# VauDUOv1_2.net
KiCad netlist of a schematic drawn in EAGLE
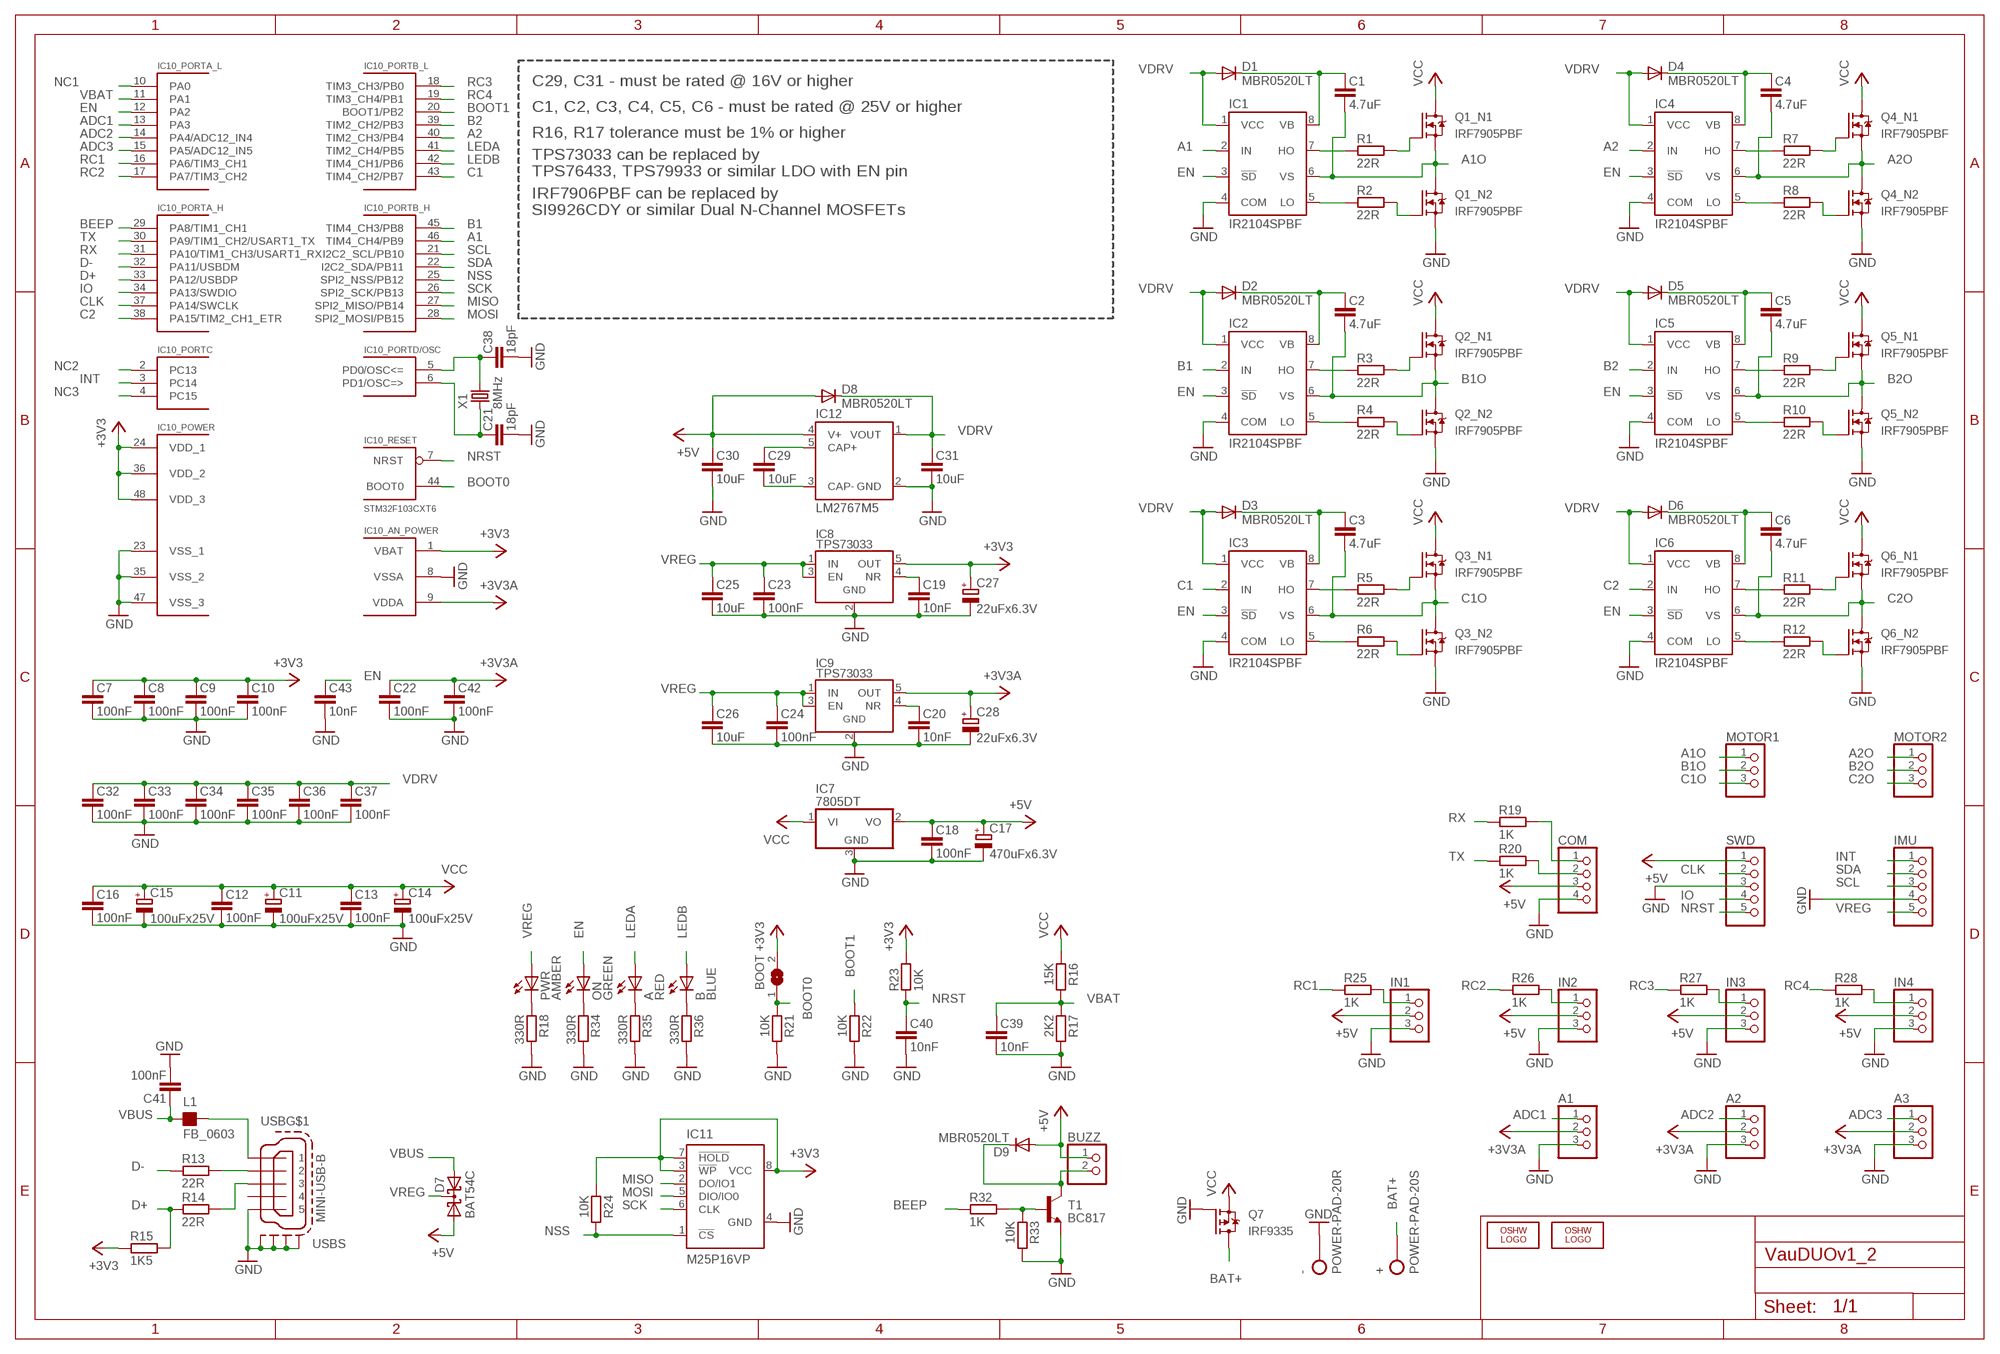
[diagram p0: schematic, sheet 1]

(export (version "E")
  (design (tool "Eeschema 10.0.6"))
  (components
    (comp (ref "+")
      (value "POWER-PAD-20S")
      (footprint "eagle-import:PAD20S")
      (libsource (lib "eagle-import") (part "POWER-PAD-20S"))
    )
    (comp (ref "-")
      (value "POWER-PAD-20R")
      (footprint "eagle-import:PAD20R")
      (libsource (lib "eagle-import") (part "POWER-PAD-20R"))
    )
    (comp (ref "A")
      (value "RED")
      (footprint "eagle-import:CHIPLED_0805")
      (libsource (lib "eagle-import") (part "LEDCHIPLED_0805"))
    )
    (comp (ref "A1")
      (value "PINHD-1X3")
      (footprint "eagle-import:1X03")
      (libsource (lib "eagle-import") (part "PINHD-1X3"))
    )
    (comp (ref "A2")
      (value "PINHD-1X3")
      (footprint "eagle-import:1X03")
      (libsource (lib "eagle-import") (part "PINHD-1X3"))
    )
    (comp (ref "A3")
      (value "PINHD-1X3")
      (footprint "eagle-import:1X03")
      (libsource (lib "eagle-import") (part "PINHD-1X3"))
    )
    (comp (ref "B")
      (value "BLUE")
      (footprint "eagle-import:CHIPLED_0805")
      (libsource (lib "eagle-import") (part "LEDCHIPLED_0805"))
    )
    (comp (ref "BOOT")
      (value "SJ")
      (footprint "eagle-import:SJ")
      (libsource (lib "eagle-import") (part "SJ"))
    )
    (comp (ref "BUZZ")
      (value "PINHD-1X2")
      (footprint "eagle-import:1X02")
      (libsource (lib "eagle-import") (part "PINHD-1X2"))
    )
    (comp (ref "C1")
      (value "4.7uF")
      (footprint "eagle-import:C0805")
      (libsource (lib "eagle-import") (part "C_EU_C0805"))
    )
    (comp (ref "C2")
      (value "4.7uF")
      (footprint "eagle-import:C0805")
      (libsource (lib "eagle-import") (part "C_EU_C0805"))
    )
    (comp (ref "C3")
      (value "4.7uF")
      (footprint "eagle-import:C0805")
      (libsource (lib "eagle-import") (part "C_EU_C0805"))
    )
    (comp (ref "C4")
      (value "4.7uF")
      (footprint "eagle-import:C0805")
      (libsource (lib "eagle-import") (part "C_EU_C0805"))
    )
    (comp (ref "C5")
      (value "4.7uF")
      (footprint "eagle-import:C0805")
      (libsource (lib "eagle-import") (part "C_EU_C0805"))
    )
    (comp (ref "C6")
      (value "4.7uF")
      (footprint "eagle-import:C0805")
      (libsource (lib "eagle-import") (part "C_EU_C0805"))
    )
    (comp (ref "C7")
      (value "100nF")
      (footprint "eagle-import:C0603G")
      (libsource (lib "eagle-import") (part "C_EU_C0603G"))
    )
    (comp (ref "C8")
      (value "100nF")
      (footprint "eagle-import:C0603G")
      (libsource (lib "eagle-import") (part "C_EU_C0603G"))
    )
    (comp (ref "C9")
      (value "100nF")
      (footprint "eagle-import:C0603G")
      (libsource (lib "eagle-import") (part "C_EU_C0603G"))
    )
    (comp (ref "C10")
      (value "100nF")
      (footprint "eagle-import:C0603G")
      (libsource (lib "eagle-import") (part "C_EU_C0603G"))
    )
    (comp (ref "C11")
      (value "100uFx25V")
      (footprint "eagle-import:E2,5-7")
      (libsource (lib "eagle-import") (part "CPOL-EUE2.5-7"))
    )
    (comp (ref "C12")
      (value "100nF")
      (footprint "eagle-import:C0603G")
      (libsource (lib "eagle-import") (part "C_EU_C0603G"))
    )
    (comp (ref "C13")
      (value "100nF")
      (footprint "eagle-import:C0603G")
      (libsource (lib "eagle-import") (part "C_EU_C0603G"))
    )
    (comp (ref "C14")
      (value "100uFx25V")
      (footprint "eagle-import:E2,5-7")
      (libsource (lib "eagle-import") (part "CPOL-EUE2.5-7"))
    )
    (comp (ref "C15")
      (value "100uFx25V")
      (footprint "eagle-import:SMC_D")
      (libsource (lib "eagle-import") (part "CPOL-EUSMCD"))
    )
    (comp (ref "C16")
      (value "100nF")
      (footprint "eagle-import:C0603G")
      (libsource (lib "eagle-import") (part "C_EU_C0603G"))
    )
    (comp (ref "C17")
      (value "470uFx6.3V")
      (footprint "eagle-import:SMC_D")
      (libsource (lib "eagle-import") (part "CPOL-EUSMCD"))
    )
    (comp (ref "C18")
      (value "100nF")
      (footprint "eagle-import:C0603G")
      (libsource (lib "eagle-import") (part "C_EU_C0603G"))
    )
    (comp (ref "C19")
      (value "10nF")
      (footprint "eagle-import:C0603G")
      (libsource (lib "eagle-import") (part "C_EU_C0603G"))
    )
    (comp (ref "C20")
      (value "10nF")
      (footprint "eagle-import:C0603G")
      (libsource (lib "eagle-import") (part "C_EU_C0603G"))
    )
    (comp (ref "C21")
      (value "18pF")
      (footprint "eagle-import:C0603G")
      (libsource (lib "eagle-import") (part "C_EU_C0603G"))
    )
    (comp (ref "C22")
      (value "100nF")
      (footprint "eagle-import:C0603G")
      (libsource (lib "eagle-import") (part "C_EU_C0603G"))
    )
    (comp (ref "C23")
      (value "100nF")
      (footprint "eagle-import:C0603G")
      (libsource (lib "eagle-import") (part "C_EU_C0603G"))
    )
    (comp (ref "C24")
      (value "100nF")
      (footprint "eagle-import:C0603G")
      (libsource (lib "eagle-import") (part "C_EU_C0603G"))
    )
    (comp (ref "C25")
      (value "10uF")
      (footprint "eagle-import:C0805G")
      (libsource (lib "eagle-import") (part "C_EU_C0805G"))
    )
    (comp (ref "C26")
      (value "10uF")
      (footprint "eagle-import:C0805G")
      (libsource (lib "eagle-import") (part "C_EU_C0805G"))
    )
    (comp (ref "C27")
      (value "22uFx6.3V")
      (footprint "eagle-import:SMC_A")
      (libsource (lib "eagle-import") (part "CPOL-EUSMCA"))
    )
    (comp (ref "C28")
      (value "22uFx6.3V")
      (footprint "eagle-import:SMC_A")
      (libsource (lib "eagle-import") (part "CPOL-EUSMCA"))
    )
    (comp (ref "C29")
      (value "10uF")
      (footprint "eagle-import:C0805")
      (libsource (lib "eagle-import") (part "C_EU_C0805"))
    )
    (comp (ref "C30")
      (value "10uF")
      (footprint "eagle-import:C0805G")
      (libsource (lib "eagle-import") (part "C_EU_C0805G"))
    )
    (comp (ref "C31")
      (value "10uF")
      (footprint "eagle-import:C0805G")
      (libsource (lib "eagle-import") (part "C_EU_C0805G"))
    )
    (comp (ref "C32")
      (value "100nF")
      (footprint "eagle-import:C0603G")
      (libsource (lib "eagle-import") (part "C_EU_C0603G"))
    )
    (comp (ref "C33")
      (value "100nF")
      (footprint "eagle-import:C0603G")
      (libsource (lib "eagle-import") (part "C_EU_C0603G"))
    )
    (comp (ref "C34")
      (value "100nF")
      (footprint "eagle-import:C0603G")
      (libsource (lib "eagle-import") (part "C_EU_C0603G"))
    )
    (comp (ref "C35")
      (value "100nF")
      (footprint "eagle-import:C0603G")
      (libsource (lib "eagle-import") (part "C_EU_C0603G"))
    )
    (comp (ref "C36")
      (value "100nF")
      (footprint "eagle-import:C0603G")
      (libsource (lib "eagle-import") (part "C_EU_C0603G"))
    )
    (comp (ref "C37")
      (value "100nF")
      (footprint "eagle-import:C0603G")
      (libsource (lib "eagle-import") (part "C_EU_C0603G"))
    )
    (comp (ref "C38")
      (value "18pF")
      (footprint "eagle-import:C0603G")
      (libsource (lib "eagle-import") (part "C_EU_C0603G"))
    )
    (comp (ref "C39")
      (value "10nF")
      (footprint "eagle-import:C0603G")
      (libsource (lib "eagle-import") (part "C_EU_C0603G"))
    )
    (comp (ref "C40")
      (value "10nF")
      (footprint "eagle-import:C0603G")
      (libsource (lib "eagle-import") (part "C_EU_C0603G"))
    )
    (comp (ref "C41")
      (value "100nF")
      (footprint "eagle-import:C0603G")
      (libsource (lib "eagle-import") (part "C_EU_C0603G"))
    )
    (comp (ref "C42")
      (value "100nF")
      (footprint "eagle-import:C0603G")
      (libsource (lib "eagle-import") (part "C_EU_C0603G"))
    )
    (comp (ref "C43")
      (value "10nF")
      (footprint "eagle-import:C0603G")
      (libsource (lib "eagle-import") (part "C_EU_C0603G"))
    )
    (comp (ref "COM")
      (value "PINHD-1X4")
      (footprint "eagle-import:1X04")
      (libsource (lib "eagle-import") (part "PINHD-1X4"))
    )
    (comp (ref "D1")
      (value "MBR0520LT")
      (footprint "eagle-import:SOD123")
      (libsource (lib "eagle-import") (part "MBR0520LT"))
    )
    (comp (ref "D2")
      (value "MBR0520LT")
      (footprint "eagle-import:SOD123")
      (libsource (lib "eagle-import") (part "MBR0520LT"))
    )
    (comp (ref "D3")
      (value "MBR0520LT")
      (footprint "eagle-import:SOD123")
      (libsource (lib "eagle-import") (part "MBR0520LT"))
    )
    (comp (ref "D4")
      (value "MBR0520LT")
      (footprint "eagle-import:SOD123")
      (libsource (lib "eagle-import") (part "MBR0520LT"))
    )
    (comp (ref "D5")
      (value "MBR0520LT")
      (footprint "eagle-import:SOD123")
      (libsource (lib "eagle-import") (part "MBR0520LT"))
    )
    (comp (ref "D6")
      (value "MBR0520LT")
      (footprint "eagle-import:SOD123")
      (libsource (lib "eagle-import") (part "MBR0520LT"))
    )
    (comp (ref "D7")
      (value "BAT54C")
      (footprint "eagle-import:SOT23")
      (libsource (lib "eagle-import") (part "BAT54C"))
    )
    (comp (ref "D8")
      (value "MBR0520LT")
      (footprint "eagle-import:SOD123")
      (libsource (lib "eagle-import") (part "MBR0520LT"))
    )
    (comp (ref "D9")
      (value "MBR0520LT")
      (footprint "eagle-import:SOD123")
      (libsource (lib "eagle-import") (part "MBR0520LT"))
    )
    (comp (ref "IC1")
      (value "IR2104SPBF")
      (footprint "eagle-import:SOIC-8")
      (libsource (lib "eagle-import") (part "IR2104SPBF"))
    )
    (comp (ref "IC2")
      (value "IR2104SPBF")
      (footprint "eagle-import:SOIC-8")
      (libsource (lib "eagle-import") (part "IR2104SPBF"))
    )
    (comp (ref "IC3")
      (value "IR2104SPBF")
      (footprint "eagle-import:SOIC-8")
      (libsource (lib "eagle-import") (part "IR2104SPBF"))
    )
    (comp (ref "IC4")
      (value "IR2104SPBF")
      (footprint "eagle-import:SOIC-8")
      (libsource (lib "eagle-import") (part "IR2104SPBF"))
    )
    (comp (ref "IC5")
      (value "IR2104SPBF")
      (footprint "eagle-import:SOIC-8")
      (libsource (lib "eagle-import") (part "IR2104SPBF"))
    )
    (comp (ref "IC6")
      (value "IR2104SPBF")
      (footprint "eagle-import:SOIC-8")
      (libsource (lib "eagle-import") (part "IR2104SPBF"))
    )
    (comp (ref "IC7")
      (value "7805DT")
      (footprint "eagle-import:TO252")
      (libsource (lib "eagle-import") (part "78DT05"))
    )
    (comp (ref "IC8")
      (value "TPS73033")
      (footprint "eagle-import:SOT23-5")
      (libsource (lib "eagle-import") (part "TPS769XX"))
    )
    (comp (ref "IC9")
      (value "TPS73033")
      (footprint "eagle-import:SOT23-5")
      (libsource (lib "eagle-import") (part "TPS769XX"))
    )
    (comp (ref "IC10")
      (value "STM32F103CXT6")
      (footprint "eagle-import:LQFP48")
      (libsource (lib "eagle-import") (part "STM32F103CXT6"))
    )
    (comp (ref "IC11")
      (value "M25P16VP")
      (footprint "eagle-import:SOIC-8")
      (libsource (lib "eagle-import") (part "W25X40BVSNIG"))
    )
    (comp (ref "IC12")
      (value "LM2767M5")
      (footprint "eagle-import:SOT23-5")
      (libsource (lib "eagle-import") (part "LM2767M5"))
    )
    (comp (ref "IMU")
      (value "PINHD-1X5")
      (footprint "eagle-import:1X05")
      (libsource (lib "eagle-import") (part "PINHD-1X5"))
    )
    (comp (ref "IN1")
      (value "PINHD-1X3")
      (footprint "eagle-import:1X03")
      (libsource (lib "eagle-import") (part "PINHD-1X3"))
    )
    (comp (ref "IN2")
      (value "PINHD-1X3")
      (footprint "eagle-import:1X03")
      (libsource (lib "eagle-import") (part "PINHD-1X3"))
    )
    (comp (ref "IN3")
      (value "PINHD-1X3")
      (footprint "eagle-import:1X03")
      (libsource (lib "eagle-import") (part "PINHD-1X3"))
    )
    (comp (ref "IN4")
      (value "PINHD-1X3")
      (footprint "eagle-import:1X03")
      (libsource (lib "eagle-import") (part "PINHD-1X3"))
    )
    (comp (ref "L1")
      (value "FB_0603")
      (footprint "eagle-import:L0603")
      (libsource (lib "eagle-import") (part "FB_0603"))
    )
    (comp (ref "LOGO1")
      (value "OSHW_LOGO_10MILX0350-NT")
      (footprint "eagle-import:OSHW_10X350_NOTEXT")
      (libsource (lib "eagle-import") (part "OSHW_LOGO_10MILX0350-NT"))
    )
    (comp (ref "LOGO2")
      (value "OSHW_LOGO_FILLX0150-NT")
      (footprint "eagle-import:OSHW_FILLX150_NOTEXT")
      (libsource (lib "eagle-import") (part "OSHW_LOGO_FILLX0150-NT"))
    )
    (comp (ref "MOTOR1")
      (value "PINHD-1X3MOT")
      (footprint "eagle-import:1X03M")
      (libsource (lib "eagle-import") (part "PINHD-1X3MOT"))
    )
    (comp (ref "MOTOR2")
      (value "PINHD-1X3MOT")
      (footprint "eagle-import:1X03M")
      (libsource (lib "eagle-import") (part "PINHD-1X3MOT"))
    )
    (comp (ref "ON")
      (value "GREEN")
      (footprint "eagle-import:CHIPLED_0805")
      (libsource (lib "eagle-import") (part "LEDCHIPLED_0805"))
    )
    (comp (ref "PWR")
      (value "AMBER")
      (footprint "eagle-import:CHIPLED_0805")
      (libsource (lib "eagle-import") (part "LEDCHIPLED_0805"))
    )
    (comp (ref "Q1")
      (value "IRF7905PBF")
      (footprint "eagle-import:SOIC-8")
      (libsource (lib "eagle-import") (part "IRF7905PBF"))
    )
    (comp (ref "Q2")
      (value "IRF7905PBF")
      (footprint "eagle-import:SOIC-8")
      (libsource (lib "eagle-import") (part "IRF7905PBF"))
    )
    (comp (ref "Q3")
      (value "IRF7905PBF")
      (footprint "eagle-import:SOIC-8")
      (libsource (lib "eagle-import") (part "IRF7905PBF"))
    )
    (comp (ref "Q4")
      (value "IRF7905PBF")
      (footprint "eagle-import:SOIC-8")
      (libsource (lib "eagle-import") (part "IRF7905PBF"))
    )
    (comp (ref "Q5")
      (value "IRF7905PBF")
      (footprint "eagle-import:SOIC-8")
      (libsource (lib "eagle-import") (part "IRF7905PBF"))
    )
    (comp (ref "Q6")
      (value "IRF7905PBF")
      (footprint "eagle-import:SOIC-8")
      (libsource (lib "eagle-import") (part "IRF7905PBF"))
    )
    (comp (ref "Q7")
      (value "IRF9335")
      (footprint "eagle-import:SOIC-8")
      (libsource (lib "eagle-import") (part "IRF9335"))
    )
    (comp (ref "R1")
      (value "22R")
      (footprint "eagle-import:R0603")
      (libsource (lib "eagle-import") (part "R_EU_R0603"))
    )
    (comp (ref "R2")
      (value "22R")
      (footprint "eagle-import:R0603")
      (libsource (lib "eagle-import") (part "R_EU_R0603"))
    )
    (comp (ref "R3")
      (value "22R")
      (footprint "eagle-import:R0603")
      (libsource (lib "eagle-import") (part "R_EU_R0603"))
    )
    (comp (ref "R4")
      (value "22R")
      (footprint "eagle-import:R0603")
      (libsource (lib "eagle-import") (part "R_EU_R0603"))
    )
    (comp (ref "R5")
      (value "22R")
      (footprint "eagle-import:R0603")
      (libsource (lib "eagle-import") (part "R_EU_R0603"))
    )
    (comp (ref "R6")
      (value "22R")
      (footprint "eagle-import:R0603")
      (libsource (lib "eagle-import") (part "R_EU_R0603"))
    )
    (comp (ref "R7")
      (value "22R")
      (footprint "eagle-import:R0603")
      (libsource (lib "eagle-import") (part "R_EU_R0603"))
    )
    (comp (ref "R8")
      (value "22R")
      (footprint "eagle-import:R0603")
      (libsource (lib "eagle-import") (part "R_EU_R0603"))
    )
    (comp (ref "R9")
      (value "22R")
      (footprint "eagle-import:R0603")
      (libsource (lib "eagle-import") (part "R_EU_R0603"))
    )
    (comp (ref "R10")
      (value "22R")
      (footprint "eagle-import:R0603")
      (libsource (lib "eagle-import") (part "R_EU_R0603"))
    )
    (comp (ref "R11")
      (value "22R")
      (footprint "eagle-import:R0603")
      (libsource (lib "eagle-import") (part "R_EU_R0603"))
    )
    (comp (ref "R12")
      (value "22R")
      (footprint "eagle-import:R0603")
      (libsource (lib "eagle-import") (part "R_EU_R0603"))
    )
    (comp (ref "R13")
      (value "22R")
      (footprint "eagle-import:R0603")
      (libsource (lib "eagle-import") (part "R_EU_R0603"))
    )
    (comp (ref "R14")
      (value "22R")
      (footprint "eagle-import:R0603")
      (libsource (lib "eagle-import") (part "R_EU_R0603"))
    )
    (comp (ref "R15")
      (value "1K5")
      (footprint "eagle-import:R0603")
      (libsource (lib "eagle-import") (part "R_EU_R0603"))
    )
    (comp (ref "R16")
      (value "15K")
      (footprint "eagle-import:R0603")
      (libsource (lib "eagle-import") (part "R_EU_R0603"))
    )
    (comp (ref "R17")
      (value "2K2")
      (footprint "eagle-import:R0603G")
      (libsource (lib "eagle-import") (part "R_EU_R0603G"))
    )
    (comp (ref "R18")
      (value "330R")
      (footprint "eagle-import:R0603G")
      (libsource (lib "eagle-import") (part "R_EU_R0603G"))
    )
    (comp (ref "R19")
      (value "1K")
      (footprint "eagle-import:R0603")
      (libsource (lib "eagle-import") (part "R_EU_R0603"))
    )
    (comp (ref "R20")
      (value "1K")
      (footprint "eagle-import:R0603")
      (libsource (lib "eagle-import") (part "R_EU_R0603"))
    )
    (comp (ref "R21")
      (value "10K")
      (footprint "eagle-import:R0603G")
      (libsource (lib "eagle-import") (part "R_EU_R0603G"))
    )
    (comp (ref "R22")
      (value "10K")
      (footprint "eagle-import:R0603G")
      (libsource (lib "eagle-import") (part "R_EU_R0603G"))
    )
    (comp (ref "R23")
      (value "10K")
      (footprint "eagle-import:R0603")
      (libsource (lib "eagle-import") (part "R_EU_R0603"))
    )
    (comp (ref "R24")
      (value "10K")
      (footprint "eagle-import:R0603")
      (libsource (lib "eagle-import") (part "R_EU_R0603"))
    )
    (comp (ref "R25")
      (value "1K")
      (footprint "eagle-import:R0603")
      (libsource (lib "eagle-import") (part "R_EU_R0603"))
    )
    (comp (ref "R26")
      (value "1K")
      (footprint "eagle-import:R0603")
      (libsource (lib "eagle-import") (part "R_EU_R0603"))
    )
    (comp (ref "R27")
      (value "1K")
      (footprint "eagle-import:R0603")
      (libsource (lib "eagle-import") (part "R_EU_R0603"))
    )
    (comp (ref "R28")
      (value "1K")
      (footprint "eagle-import:R0603")
      (libsource (lib "eagle-import") (part "R_EU_R0603"))
    )
    (comp (ref "R32")
      (value "1K")
      (footprint "eagle-import:R0603")
      (libsource (lib "eagle-import") (part "R_EU_R0603"))
    )
    (comp (ref "R33")
      (value "10K")
      (footprint "eagle-import:R0603G")
      (libsource (lib "eagle-import") (part "R_EU_R0603G"))
    )
    (comp (ref "R34")
      (value "330R")
      (footprint "eagle-import:R0603G")
      (libsource (lib "eagle-import") (part "R_EU_R0603G"))
    )
    (comp (ref "R35")
      (value "330R")
      (footprint "eagle-import:R0603G")
      (libsource (lib "eagle-import") (part "R_EU_R0603G"))
    )
    (comp (ref "R36")
      (value "330R")
      (footprint "eagle-import:R0603G")
      (libsource (lib "eagle-import") (part "R_EU_R0603G"))
    )
    (comp (ref "SWD")
      (value "PINHD-1X5")
      (footprint "eagle-import:1X05")
      (libsource (lib "eagle-import") (part "PINHD-1X5"))
    )
    (comp (ref "T1")
      (value "BC817")
      (footprint "eagle-import:SOT23-BEC")
      (libsource (lib "eagle-import") (part "BC817SMD-16LT1"))
    )
    (comp (ref "USB")
      (value "MINI-USB-B")
      (footprint "eagle-import:32005-201")
      (libsource (lib "eagle-import") (part "MINI-USB-SCHIELD-32005-201"))
    )
    (comp (ref "X1")
      (value "8MHz")
      (footprint "eagle-import:HC49_S")
      (libsource (lib "eagle-import") (part "CRYSTALHC49S"))
    )
  )
  (nets
    (net (code "1") (name "+3V3") (class "Default")
      (node (ref "BOOT") (pin "2") (pinfunction "2_2") (pintype "passive"))
      (node (ref "C10") (pin "1") (pinfunction "1_1") (pintype "passive"))
      (node (ref "C27") (pin "+") (pinfunction "+_+") (pintype "passive"))
      (node (ref "C7") (pin "1") (pinfunction "1_1") (pintype "passive"))
      (node (ref "C8") (pin "1") (pinfunction "1_1") (pintype "passive"))
      (node (ref "C9") (pin "1") (pinfunction "1_1") (pintype "passive"))
      (node (ref "IC10") (pin "1") (pinfunction "VBAT_1") (pintype "power_in"))
      (node (ref "IC10") (pin "24") (pinfunction "VDD_1_24") (pintype "power_in"))
      (node (ref "IC10") (pin "36") (pinfunction "VDD_2_36") (pintype "power_in"))
      (node (ref "IC10") (pin "48") (pinfunction "VDD_3_48") (pintype "power_in"))
      (node (ref "IC11") (pin "3") (pinfunction "~{WP}_3") (pintype "input"))
      (node (ref "IC11") (pin "7") (pinfunction "~{HOLD}_7") (pintype "input"))
      (node (ref "IC11") (pin "8") (pinfunction "VCC_8") (pintype "power_in"))
      (node (ref "IC8") (pin "5") (pinfunction "OUT_5") (pintype "power_in"))
      (node (ref "R15") (pin "1") (pinfunction "1_1") (pintype "passive"))
      (node (ref "R23") (pin "2") (pinfunction "2_2") (pintype "passive"))
      (node (ref "R24") (pin "1") (pinfunction "1_1") (pintype "passive"))
    )
    (net (code "2") (name "+3V3A") (class "Default")
      (node (ref "A1") (pin "2") (pinfunction "2_2") (pintype "passive"))
      (node (ref "A2") (pin "2") (pinfunction "2_2") (pintype "passive"))
      (node (ref "A3") (pin "2") (pinfunction "2_2") (pintype "passive"))
      (node (ref "C22") (pin "1") (pinfunction "1_1") (pintype "passive"))
      (node (ref "C28") (pin "+") (pinfunction "+_+") (pintype "passive"))
      (node (ref "C42") (pin "1") (pinfunction "1_1") (pintype "passive"))
      (node (ref "IC10") (pin "9") (pinfunction "VDDA_9") (pintype "power_in"))
      (node (ref "IC9") (pin "5") (pinfunction "OUT_5") (pintype "power_in"))
    )
    (net (code "3") (name "+5V") (class "Default")
      (node (ref "BUZZ") (pin "1") (pinfunction "1_1") (pintype "passive"))
      (node (ref "C17") (pin "+") (pinfunction "+_+") (pintype "passive"))
      (node (ref "C18") (pin "1") (pinfunction "1_1") (pintype "passive"))
      (node (ref "C30") (pin "1") (pinfunction "1_1") (pintype "passive"))
      (node (ref "COM") (pin "3") (pinfunction "3_3") (pintype "passive"))
      (node (ref "D7") (pin "1") (pinfunction "A1_1") (pintype "passive"))
      (node (ref "D8") (pin "A") (pinfunction "A_A") (pintype "passive"))
      (node (ref "D9") (pin "A") (pinfunction "A_A") (pintype "passive"))
      (node (ref "IC12") (pin "4") (pinfunction "V+_4") (pintype "input"))
      (node (ref "IC7") (pin "2") (pinfunction "VO_2") (pintype "passive"))
      (node (ref "IN1") (pin "2") (pinfunction "2_2") (pintype "passive"))
      (node (ref "IN2") (pin "2") (pinfunction "2_2") (pintype "passive"))
      (node (ref "IN3") (pin "2") (pinfunction "2_2") (pintype "passive"))
      (node (ref "IN4") (pin "2") (pinfunction "2_2") (pintype "passive"))
      (node (ref "SWD") (pin "1") (pinfunction "1_1") (pintype "passive"))
    )
    (net (code "4") (name "/A1") (class "Default")
      (node (ref "IC1") (pin "2") (pinfunction "IN_2") (pintype "input"))
      (node (ref "IC10") (pin "46") (pinfunction "TIM4_CH4/PB9_46") (pintype "bidirectional"))
    )
    (net (code "5") (name "/A1O") (class "Default")
      (node (ref "C1") (pin "2") (pinfunction "2_2") (pintype "passive"))
      (node (ref "IC1") (pin "6") (pinfunction "VS_6") (pintype "input"))
      (node (ref "MOTOR1") (pin "1") (pinfunction "1_1") (pintype "passive"))
      (node (ref "Q1") (pin "3") (pinfunction "N-S_3") (pintype "passive"))
      (node (ref "Q1") (pin "7") (pinfunction "N-D_7") (pintype "passive"))
      (node (ref "Q1") (pin "8") (pinfunction "N-D_8") (pintype "passive"))
    )
    (net (code "6") (name "/A2") (class "Default")
      (node (ref "IC10") (pin "40") (pinfunction "TIM2_CH3/PB4_40") (pintype "bidirectional"))
      (node (ref "IC4") (pin "2") (pinfunction "IN_2") (pintype "input"))
    )
    (net (code "7") (name "/A2O") (class "Default")
      (node (ref "C4") (pin "2") (pinfunction "2_2") (pintype "passive"))
      (node (ref "IC4") (pin "6") (pinfunction "VS_6") (pintype "input"))
      (node (ref "MOTOR2") (pin "1") (pinfunction "1_1") (pintype "passive"))
      (node (ref "Q4") (pin "3") (pinfunction "N-S_3") (pintype "passive"))
      (node (ref "Q4") (pin "7") (pinfunction "N-D_7") (pintype "passive"))
      (node (ref "Q4") (pin "8") (pinfunction "N-D_8") (pintype "passive"))
    )
    (net (code "8") (name "/ADC1") (class "Default")
      (node (ref "A1") (pin "1") (pinfunction "1_1") (pintype "passive"))
      (node (ref "IC10") (pin "13") (pinfunction "PA3_13") (pintype "bidirectional"))
    )
    (net (code "9") (name "/ADC2") (class "Default")
      (node (ref "A2") (pin "1") (pinfunction "1_1") (pintype "passive"))
      (node (ref "IC10") (pin "14") (pinfunction "PA4/ADC12_IN4_14") (pintype "bidirectional"))
    )
    (net (code "10") (name "/ADC3") (class "Default")
      (node (ref "A3") (pin "1") (pinfunction "1_1") (pintype "passive"))
      (node (ref "IC10") (pin "15") (pinfunction "PA5/ADC12_IN5_15") (pintype "bidirectional"))
    )
    (net (code "11") (name "/B1") (class "Default")
      (node (ref "IC10") (pin "45") (pinfunction "TIM4_CH3/PB8_45") (pintype "bidirectional"))
      (node (ref "IC2") (pin "2") (pinfunction "IN_2") (pintype "input"))
    )
    (net (code "12") (name "/B1O") (class "Default")
      (node (ref "C2") (pin "2") (pinfunction "2_2") (pintype "passive"))
      (node (ref "IC2") (pin "6") (pinfunction "VS_6") (pintype "input"))
      (node (ref "MOTOR1") (pin "2") (pinfunction "2_2") (pintype "passive"))
      (node (ref "Q2") (pin "3") (pinfunction "N-S_3") (pintype "passive"))
      (node (ref "Q2") (pin "7") (pinfunction "N-D_7") (pintype "passive"))
      (node (ref "Q2") (pin "8") (pinfunction "N-D_8") (pintype "passive"))
    )
    (net (code "13") (name "/B2") (class "Default")
      (node (ref "IC10") (pin "39") (pinfunction "TIM2_CH2/PB3_39") (pintype "bidirectional"))
      (node (ref "IC5") (pin "2") (pinfunction "IN_2") (pintype "input"))
    )
    (net (code "14") (name "/B2O") (class "Default")
      (node (ref "C5") (pin "2") (pinfunction "2_2") (pintype "passive"))
      (node (ref "IC5") (pin "6") (pinfunction "VS_6") (pintype "input"))
      (node (ref "MOTOR2") (pin "2") (pinfunction "2_2") (pintype "passive"))
      (node (ref "Q5") (pin "3") (pinfunction "N-S_3") (pintype "passive"))
      (node (ref "Q5") (pin "7") (pinfunction "N-D_7") (pintype "passive"))
      (node (ref "Q5") (pin "8") (pinfunction "N-D_8") (pintype "passive"))
    )
    (net (code "15") (name "/BAT+") (class "Default")
      (node (ref "+") (pin "P$1") (pinfunction "1_P$1") (pintype "bidirectional"))
      (node (ref "Q7") (pin "5") (pinfunction "P-D_5") (pintype "passive"))
      (node (ref "Q7") (pin "6") (pinfunction "P-D_6") (pintype "passive"))
      (node (ref "Q7") (pin "7") (pinfunction "P-D_7") (pintype "passive"))
      (node (ref "Q7") (pin "8") (pinfunction "P-D_8") (pintype "passive"))
    )
    (net (code "16") (name "/BEEP") (class "Default")
      (node (ref "IC10") (pin "29") (pinfunction "PA8/TIM1_CH1_29") (pintype "bidirectional"))
      (node (ref "R32") (pin "1") (pinfunction "1_1") (pintype "passive"))
    )
    (net (code "17") (name "/BOOT0") (class "Default")
      (node (ref "BOOT") (pin "1") (pinfunction "1_1") (pintype "passive"))
      (node (ref "IC10") (pin "44") (pinfunction "BOOT0_44") (pintype "input"))
      (node (ref "R21") (pin "1") (pinfunction "1_1") (pintype "passive"))
    )
    (net (code "18") (name "/BOOT1") (class "Default")
      (node (ref "IC10") (pin "20") (pinfunction "BOOT1/PB2_20") (pintype "bidirectional"))
      (node (ref "R22") (pin "1") (pinfunction "1_1") (pintype "passive"))
    )
    (net (code "19") (name "/C1") (class "Default")
      (node (ref "IC10") (pin "43") (pinfunction "TIM4_CH2/PB7_43") (pintype "bidirectional"))
      (node (ref "IC3") (pin "2") (pinfunction "IN_2") (pintype "input"))
    )
    (net (code "20") (name "/C1O") (class "Default")
      (node (ref "C3") (pin "2") (pinfunction "2_2") (pintype "passive"))
      (node (ref "IC3") (pin "6") (pinfunction "VS_6") (pintype "input"))
      (node (ref "MOTOR1") (pin "3") (pinfunction "3_3") (pintype "passive"))
      (node (ref "Q3") (pin "3") (pinfunction "N-S_3") (pintype "passive"))
      (node (ref "Q3") (pin "7") (pinfunction "N-D_7") (pintype "passive"))
      (node (ref "Q3") (pin "8") (pinfunction "N-D_8") (pintype "passive"))
    )
    (net (code "21") (name "/C2") (class "Default")
      (node (ref "IC10") (pin "38") (pinfunction "PA15/TIM2_CH1_ETR_38") (pintype "bidirectional"))
      (node (ref "IC6") (pin "2") (pinfunction "IN_2") (pintype "input"))
    )
    (net (code "22") (name "/C2O") (class "Default")
      (node (ref "C6") (pin "2") (pinfunction "2_2") (pintype "passive"))
      (node (ref "IC6") (pin "6") (pinfunction "VS_6") (pintype "input"))
      (node (ref "MOTOR2") (pin "3") (pinfunction "3_3") (pintype "passive"))
      (node (ref "Q6") (pin "3") (pinfunction "N-S_3") (pintype "passive"))
      (node (ref "Q6") (pin "7") (pinfunction "N-D_7") (pintype "passive"))
      (node (ref "Q6") (pin "8") (pinfunction "N-D_8") (pintype "passive"))
    )
    (net (code "23") (name "/CLK") (class "Default")
      (node (ref "IC10") (pin "37") (pinfunction "PA14/SWCLK_37") (pintype "bidirectional"))
      (node (ref "SWD") (pin "2") (pinfunction "2_2") (pintype "passive"))
    )
    (net (code "24") (name "/D+") (class "Default")
      (node (ref "IC10") (pin "33") (pinfunction "PA12/USBDP_33") (pintype "bidirectional"))
      (node (ref "R14") (pin "1") (pinfunction "1_1") (pintype "passive"))
      (node (ref "R15") (pin "2") (pinfunction "2_2") (pintype "passive"))
    )
    (net (code "25") (name "/D-") (class "Default")
      (node (ref "IC10") (pin "32") (pinfunction "PA11/USBDM_32") (pintype "bidirectional"))
      (node (ref "R13") (pin "1") (pinfunction "1_1") (pintype "passive"))
    )
    (net (code "26") (name "/EN") (class "Default")
      (node (ref "C43") (pin "1") (pinfunction "1_1") (pintype "passive"))
      (node (ref "IC1") (pin "3") (pinfunction "~{SD}_3") (pintype "input"))
      (node (ref "IC10") (pin "12") (pinfunction "PA2_12") (pintype "bidirectional"))
      (node (ref "IC2") (pin "3") (pinfunction "~{SD}_3") (pintype "input"))
      (node (ref "IC3") (pin "3") (pinfunction "~{SD}_3") (pintype "input"))
      (node (ref "IC4") (pin "3") (pinfunction "~{SD}_3") (pintype "input"))
      (node (ref "IC5") (pin "3") (pinfunction "~{SD}_3") (pintype "input"))
      (node (ref "IC6") (pin "3") (pinfunction "~{SD}_3") (pintype "input"))
      (node (ref "ON") (pin "A") (pinfunction "A_A") (pintype "passive"))
    )
    (net (code "27") (name "/INT") (class "Default")
      (node (ref "IC10") (pin "3") (pinfunction "PC14_3") (pintype "bidirectional"))
      (node (ref "IMU") (pin "1") (pinfunction "1_1") (pintype "passive"))
    )
    (net (code "28") (name "/IO") (class "Default")
      (node (ref "IC10") (pin "34") (pinfunction "PA13/SWDIO_34") (pintype "bidirectional"))
      (node (ref "SWD") (pin "4") (pinfunction "4_4") (pintype "passive"))
    )
    (net (code "29") (name "/LEDA") (class "Default")
      (node (ref "A") (pin "A") (pinfunction "A_A") (pintype "passive"))
      (node (ref "IC10") (pin "41") (pinfunction "TIM2_CH4/PB5_41") (pintype "bidirectional"))
    )
    (net (code "30") (name "/LEDB") (class "Default")
      (node (ref "B") (pin "A") (pinfunction "A_A") (pintype "passive"))
      (node (ref "IC10") (pin "42") (pinfunction "TIM4_CH1/PB6_42") (pintype "bidirectional"))
    )
    (net (code "31") (name "/MISO") (class "Default")
      (node (ref "IC10") (pin "27") (pinfunction "SPI2_MISO/PB14_27") (pintype "bidirectional"))
      (node (ref "IC11") (pin "2") (pinfunction "DO/IO1_2") (pintype "output"))
    )
    (net (code "32") (name "/MOSI") (class "Default")
      (node (ref "IC10") (pin "28") (pinfunction "SPI2_MOSI/PB15_28") (pintype "bidirectional"))
      (node (ref "IC11") (pin "5") (pinfunction "DIO/IO0_5") (pintype "bidirectional"))
    )
    (net (code "33") (name "/NC1") (class "Default")
      (node (ref "IC10") (pin "10") (pinfunction "PA0_10") (pintype "bidirectional"))
    )
    (net (code "34") (name "/NC2") (class "Default")
      (node (ref "IC10") (pin "2") (pinfunction "PC13_2") (pintype "bidirectional"))
    )
    (net (code "35") (name "/NC3") (class "Default")
      (node (ref "IC10") (pin "4") (pinfunction "PC15_4") (pintype "bidirectional"))
    )
    (net (code "36") (name "/NRST") (class "Default")
      (node (ref "C40") (pin "1") (pinfunction "1_1") (pintype "passive"))
      (node (ref "IC10") (pin "7") (pinfunction "NRST_7") (pintype "input"))
      (node (ref "R23") (pin "1") (pinfunction "1_1") (pintype "passive"))
      (node (ref "SWD") (pin "5") (pinfunction "5_5") (pintype "passive"))
    )
    (net (code "37") (name "/NSS") (class "Default")
      (node (ref "IC10") (pin "25") (pinfunction "SPI2_NSS/PB12_25") (pintype "bidirectional"))
      (node (ref "IC11") (pin "1") (pinfunction "~{CS}_1") (pintype "input"))
      (node (ref "R24") (pin "2") (pinfunction "2_2") (pintype "passive"))
    )
    (net (code "38") (name "/RC1") (class "Default")
      (node (ref "IC10") (pin "16") (pinfunction "PA6/TIM3_CH1_16") (pintype "bidirectional"))
      (node (ref "R25") (pin "1") (pinfunction "1_1") (pintype "passive"))
    )
    (net (code "39") (name "/RC2") (class "Default")
      (node (ref "IC10") (pin "17") (pinfunction "PA7/TIM3_CH2_17") (pintype "bidirectional"))
      (node (ref "R26") (pin "1") (pinfunction "1_1") (pintype "passive"))
    )
    (net (code "40") (name "/RC3") (class "Default")
      (node (ref "IC10") (pin "18") (pinfunction "TIM3_CH3/PB0_18") (pintype "bidirectional"))
      (node (ref "R27") (pin "1") (pinfunction "1_1") (pintype "passive"))
    )
    (net (code "41") (name "/RC4") (class "Default")
      (node (ref "IC10") (pin "19") (pinfunction "TIM3_CH4/PB1_19") (pintype "bidirectional"))
      (node (ref "R28") (pin "1") (pinfunction "1_1") (pintype "passive"))
    )
    (net (code "42") (name "/RX") (class "Default")
      (node (ref "IC10") (pin "31") (pinfunction "PA10/TIM1_CH3/USART1_RX_31") (pintype "bidirectional"))
      (node (ref "R19") (pin "1") (pinfunction "1_1") (pintype "passive"))
    )
    (net (code "43") (name "/SCK") (class "Default")
      (node (ref "IC10") (pin "26") (pinfunction "SPI2_SCK/PB13_26") (pintype "bidirectional"))
      (node (ref "IC11") (pin "6") (pinfunction "CLK_6") (pintype "input"))
    )
    (net (code "44") (name "/SCL") (class "Default")
      (node (ref "IC10") (pin "21") (pinfunction "I2C2_SCL/PB10_21") (pintype "bidirectional"))
      (node (ref "IMU") (pin "3") (pinfunction "3_3") (pintype "passive"))
    )
    (net (code "45") (name "/SDA") (class "Default")
      (node (ref "IC10") (pin "22") (pinfunction "I2C2_SDA/PB11_22") (pintype "bidirectional"))
      (node (ref "IMU") (pin "2") (pinfunction "2_2") (pintype "passive"))
    )
    (net (code "46") (name "/TX") (class "Default")
      (node (ref "IC10") (pin "30") (pinfunction "PA9/TIM1_CH2/USART1_TX_30") (pintype "bidirectional"))
      (node (ref "R20") (pin "1") (pinfunction "1_1") (pintype "passive"))
    )
    (net (code "47") (name "/VBAT") (class "Default")
      (node (ref "C39") (pin "1") (pinfunction "1_1") (pintype "passive"))
      (node (ref "IC10") (pin "11") (pinfunction "PA1_11") (pintype "bidirectional"))
      (node (ref "R16") (pin "2") (pinfunction "2_2") (pintype "passive"))
      (node (ref "R17") (pin "1") (pinfunction "1_1") (pintype "passive"))
    )
    (net (code "48") (name "/VBUS") (class "Default")
      (node (ref "C41") (pin "1") (pinfunction "1_1") (pintype "passive"))
      (node (ref "D7") (pin "2") (pinfunction "A2_2") (pintype "passive"))
      (node (ref "L1") (pin "1") (pinfunction "1_1") (pintype "passive"))
    )
    (net (code "49") (name "/VDRV") (class "Default")
      (node (ref "C31") (pin "1") (pinfunction "1_1") (pintype "passive"))
      (node (ref "C32") (pin "1") (pinfunction "1_1") (pintype "passive"))
      (node (ref "C33") (pin "1") (pinfunction "1_1") (pintype "passive"))
      (node (ref "C34") (pin "1") (pinfunction "1_1") (pintype "passive"))
      (node (ref "C35") (pin "1") (pinfunction "1_1") (pintype "passive"))
      (node (ref "C36") (pin "1") (pinfunction "1_1") (pintype "passive"))
      (node (ref "C37") (pin "1") (pinfunction "1_1") (pintype "passive"))
      (node (ref "D1") (pin "A") (pinfunction "A_A") (pintype "passive"))
      (node (ref "D2") (pin "A") (pinfunction "A_A") (pintype "passive"))
      (node (ref "D3") (pin "A") (pinfunction "A_A") (pintype "passive"))
      (node (ref "D4") (pin "A") (pinfunction "A_A") (pintype "passive"))
      (node (ref "D5") (pin "A") (pinfunction "A_A") (pintype "passive"))
      (node (ref "D6") (pin "A") (pinfunction "A_A") (pintype "passive"))
      (node (ref "D8") (pin "C") (pinfunction "C_C") (pintype "passive"))
      (node (ref "IC1") (pin "1") (pinfunction "VCC_1") (pintype "input"))
      (node (ref "IC12") (pin "1") (pinfunction "VOUT_1") (pintype "output"))
      (node (ref "IC2") (pin "1") (pinfunction "VCC_1") (pintype "input"))
      (node (ref "IC3") (pin "1") (pinfunction "VCC_1") (pintype "input"))
      (node (ref "IC4") (pin "1") (pinfunction "VCC_1") (pintype "input"))
      (node (ref "IC5") (pin "1") (pinfunction "VCC_1") (pintype "input"))
      (node (ref "IC6") (pin "1") (pinfunction "VCC_1") (pintype "input"))
    )
    (net (code "50") (name "/VREG") (class "Default")
      (node (ref "C23") (pin "1") (pinfunction "1_1") (pintype "passive"))
      (node (ref "C24") (pin "1") (pinfunction "1_1") (pintype "passive"))
      (node (ref "C25") (pin "1") (pinfunction "1_1") (pintype "passive"))
      (node (ref "C26") (pin "1") (pinfunction "1_1") (pintype "passive"))
      (node (ref "D7") (pin "3") (pinfunction "CC_3") (pintype "passive"))
      (node (ref "IC8") (pin "1") (pinfunction "IN_1") (pintype "power_in"))
      (node (ref "IC8") (pin "3") (pinfunction "EN_3") (pintype "passive"))
      (node (ref "IC9") (pin "1") (pinfunction "IN_1") (pintype "power_in"))
      (node (ref "IC9") (pin "3") (pinfunction "EN_3") (pintype "passive"))
      (node (ref "IMU") (pin "5") (pinfunction "5_5") (pintype "passive"))
      (node (ref "PWR") (pin "A") (pinfunction "A_A") (pintype "passive"))
    )
    (net (code "51") (name "GND") (class "Default")
      (node (ref "-") (pin "P$1") (pinfunction "1_P$1") (pintype "bidirectional"))
      (node (ref "A1") (pin "3") (pinfunction "3_3") (pintype "passive"))
      (node (ref "A2") (pin "3") (pinfunction "3_3") (pintype "passive"))
      (node (ref "A3") (pin "3") (pinfunction "3_3") (pintype "passive"))
      (node (ref "C10") (pin "2") (pinfunction "2_2") (pintype "passive"))
      (node (ref "C11") (pin "-") (pinfunction "-_-") (pintype "passive"))
      (node (ref "C12") (pin "2") (pinfunction "2_2") (pintype "passive"))
      (node (ref "C13") (pin "2") (pinfunction "2_2") (pintype "passive"))
      (node (ref "C14") (pin "-") (pinfunction "-_-") (pintype "passive"))
      (node (ref "C15") (pin "-") (pinfunction "-_-") (pintype "passive"))
      (node (ref "C16") (pin "2") (pinfunction "2_2") (pintype "passive"))
      (node (ref "C17") (pin "-") (pinfunction "-_-") (pintype "passive"))
      (node (ref "C18") (pin "2") (pinfunction "2_2") (pintype "passive"))
      (node (ref "C19") (pin "2") (pinfunction "2_2") (pintype "passive"))
      (node (ref "C20") (pin "2") (pinfunction "2_2") (pintype "passive"))
      (node (ref "C21") (pin "2") (pinfunction "2_2") (pintype "passive"))
      (node (ref "C22") (pin "2") (pinfunction "2_2") (pintype "passive"))
      (node (ref "C23") (pin "2") (pinfunction "2_2") (pintype "passive"))
      (node (ref "C24") (pin "2") (pinfunction "2_2") (pintype "passive"))
      (node (ref "C25") (pin "2") (pinfunction "2_2") (pintype "passive"))
      (node (ref "C26") (pin "2") (pinfunction "2_2") (pintype "passive"))
      (node (ref "C27") (pin "-") (pinfunction "-_-") (pintype "passive"))
      (node (ref "C28") (pin "-") (pinfunction "-_-") (pintype "passive"))
      (node (ref "C30") (pin "2") (pinfunction "2_2") (pintype "passive"))
      (node (ref "C31") (pin "2") (pinfunction "2_2") (pintype "passive"))
      (node (ref "C32") (pin "2") (pinfunction "2_2") (pintype "passive"))
      (node (ref "C33") (pin "2") (pinfunction "2_2") (pintype "passive"))
      (node (ref "C34") (pin "2") (pinfunction "2_2") (pintype "passive"))
      (node (ref "C35") (pin "2") (pinfunction "2_2") (pintype "passive"))
      (node (ref "C36") (pin "2") (pinfunction "2_2") (pintype "passive"))
      (node (ref "C37") (pin "2") (pinfunction "2_2") (pintype "passive"))
      (node (ref "C38") (pin "2") (pinfunction "2_2") (pintype "passive"))
      (node (ref "C39") (pin "2") (pinfunction "2_2") (pintype "passive"))
      (node (ref "C40") (pin "2") (pinfunction "2_2") (pintype "passive"))
      (node (ref "C41") (pin "2") (pinfunction "2_2") (pintype "passive"))
      (node (ref "C42") (pin "2") (pinfunction "2_2") (pintype "passive"))
      (node (ref "C43") (pin "2") (pinfunction "2_2") (pintype "passive"))
      (node (ref "C7") (pin "2") (pinfunction "2_2") (pintype "passive"))
      (node (ref "C8") (pin "2") (pinfunction "2_2") (pintype "passive"))
      (node (ref "C9") (pin "2") (pinfunction "2_2") (pintype "passive"))
      (node (ref "COM") (pin "4") (pinfunction "4_4") (pintype "passive"))
      (node (ref "IC1") (pin "4") (pinfunction "COM_4") (pintype "power_in"))
      (node (ref "IC10") (pin "23") (pinfunction "VSS_1_23") (pintype "power_in"))
      (node (ref "IC10") (pin "35") (pinfunction "VSS_2_35") (pintype "power_in"))
      (node (ref "IC10") (pin "47") (pinfunction "VSS_3_47") (pintype "power_in"))
      (node (ref "IC10") (pin "8") (pinfunction "VSSA_8") (pintype "power_in"))
      (node (ref "IC11") (pin "4") (pinfunction "GND_4") (pintype "power_in"))
      (node (ref "IC12") (pin "2") (pinfunction "GND_2") (pintype "power_in"))
      (node (ref "IC2") (pin "4") (pinfunction "COM_4") (pintype "power_in"))
      (node (ref "IC3") (pin "4") (pinfunction "COM_4") (pintype "power_in"))
      (node (ref "IC4") (pin "4") (pinfunction "COM_4") (pintype "power_in"))
      (node (ref "IC5") (pin "4") (pinfunction "COM_4") (pintype "power_in"))
      (node (ref "IC6") (pin "4") (pinfunction "COM_4") (pintype "power_in"))
      (node (ref "IC7") (pin "3") (pinfunction "GND_3") (pintype "passive"))
      (node (ref "IC8") (pin "2") (pinfunction "GND_2") (pintype "power_in"))
      (node (ref "IC9") (pin "2") (pinfunction "GND_2") (pintype "power_in"))
      (node (ref "IMU") (pin "4") (pinfunction "4_4") (pintype "passive"))
      (node (ref "IN1") (pin "3") (pinfunction "3_3") (pintype "passive"))
      (node (ref "IN2") (pin "3") (pinfunction "3_3") (pintype "passive"))
      (node (ref "IN3") (pin "3") (pinfunction "3_3") (pintype "passive"))
      (node (ref "IN4") (pin "3") (pinfunction "3_3") (pintype "passive"))
      (node (ref "Q1") (pin "1") (pinfunction "N-S_1") (pintype "passive"))
      (node (ref "Q2") (pin "1") (pinfunction "N-S_1") (pintype "passive"))
      (node (ref "Q3") (pin "1") (pinfunction "N-S_1") (pintype "passive"))
      (node (ref "Q4") (pin "1") (pinfunction "N-S_1") (pintype "passive"))
      (node (ref "Q5") (pin "1") (pinfunction "N-S_1") (pintype "passive"))
      (node (ref "Q6") (pin "1") (pinfunction "N-S_1") (pintype "passive"))
      (node (ref "Q7") (pin "4") (pinfunction "P-G_4") (pintype "passive"))
      (node (ref "R17") (pin "2") (pinfunction "2_2") (pintype "passive"))
      (node (ref "R18") (pin "2") (pinfunction "2_2") (pintype "passive"))
      (node (ref "R21") (pin "2") (pinfunction "2_2") (pintype "passive"))
      (node (ref "R22") (pin "2") (pinfunction "2_2") (pintype "passive"))
      (node (ref "R33") (pin "2") (pinfunction "2_2") (pintype "passive"))
      (node (ref "R34") (pin "2") (pinfunction "2_2") (pintype "passive"))
      (node (ref "R35") (pin "2") (pinfunction "2_2") (pintype "passive"))
      (node (ref "R36") (pin "2") (pinfunction "2_2") (pintype "passive"))
      (node (ref "SWD") (pin "3") (pinfunction "3_3") (pintype "passive"))
      (node (ref "T1") (pin "E") (pinfunction "E_E") (pintype "passive"))
      (node (ref "USB") (pin "5") (pinfunction "5_5") (pintype "passive"))
      (node (ref "USB") (pin "M1") (pinfunction "S1_M1") (pintype "passive"))
      (node (ref "USB") (pin "M2") (pinfunction "S2_M2") (pintype "passive"))
      (node (ref "USB") (pin "M3") (pinfunction "S3_M3") (pintype "passive"))
      (node (ref "USB") (pin "M4") (pinfunction "S4_M4") (pintype "passive"))
    )
    (net (code "52") (name "Net-(A-PadC)") (class "Default")
      (node (ref "A") (pin "C") (pinfunction "C_C") (pintype "passive"))
      (node (ref "R35") (pin "1") (pinfunction "1_1") (pintype "passive"))
    )
    (net (code "53") (name "Net-(B-PadC)") (class "Default")
      (node (ref "B") (pin "C") (pinfunction "C_C") (pintype "passive"))
      (node (ref "R36") (pin "1") (pinfunction "1_1") (pintype "passive"))
    )
    (net (code "54") (name "Net-(BUZZ-Pad2)") (class "Default")
      (node (ref "BUZZ") (pin "2") (pinfunction "2_2") (pintype "passive"))
      (node (ref "D9") (pin "C") (pinfunction "C_C") (pintype "passive"))
      (node (ref "T1") (pin "C") (pinfunction "C_C") (pintype "passive"))
    )
    (net (code "55") (name "Net-(COM-Pad1)") (class "Default")
      (node (ref "COM") (pin "1") (pinfunction "1_1") (pintype "passive"))
      (node (ref "R19") (pin "2") (pinfunction "2_2") (pintype "passive"))
    )
    (net (code "56") (name "Net-(COM-Pad2)") (class "Default")
      (node (ref "COM") (pin "2") (pinfunction "2_2") (pintype "passive"))
      (node (ref "R20") (pin "2") (pinfunction "2_2") (pintype "passive"))
    )
    (net (code "57") (name "Net-(IC1-HO)") (class "Default")
      (node (ref "IC1") (pin "7") (pinfunction "HO_7") (pintype "output"))
      (node (ref "R1") (pin "1") (pinfunction "1_1") (pintype "passive"))
    )
    (net (code "58") (name "Net-(IC1-LO)") (class "Default")
      (node (ref "IC1") (pin "5") (pinfunction "LO_5") (pintype "output"))
      (node (ref "R2") (pin "1") (pinfunction "1_1") (pintype "passive"))
    )
    (net (code "59") (name "Net-(IC1-VB)") (class "Default")
      (node (ref "C1") (pin "1") (pinfunction "1_1") (pintype "passive"))
      (node (ref "D1") (pin "C") (pinfunction "C_C") (pintype "passive"))
      (node (ref "IC1") (pin "8") (pinfunction "VB_8") (pintype "input"))
    )
    (net (code "60") (name "Net-(IC2-HO)") (class "Default")
      (node (ref "IC2") (pin "7") (pinfunction "HO_7") (pintype "output"))
      (node (ref "R3") (pin "1") (pinfunction "1_1") (pintype "passive"))
    )
    (net (code "61") (name "Net-(IC2-LO)") (class "Default")
      (node (ref "IC2") (pin "5") (pinfunction "LO_5") (pintype "output"))
      (node (ref "R4") (pin "1") (pinfunction "1_1") (pintype "passive"))
    )
    (net (code "62") (name "Net-(IC2-VB)") (class "Default")
      (node (ref "C2") (pin "1") (pinfunction "1_1") (pintype "passive"))
      (node (ref "D2") (pin "C") (pinfunction "C_C") (pintype "passive"))
      (node (ref "IC2") (pin "8") (pinfunction "VB_8") (pintype "input"))
    )
    (net (code "63") (name "Net-(IC3-HO)") (class "Default")
      (node (ref "IC3") (pin "7") (pinfunction "HO_7") (pintype "output"))
      (node (ref "R5") (pin "1") (pinfunction "1_1") (pintype "passive"))
    )
    (net (code "64") (name "Net-(IC3-LO)") (class "Default")
      (node (ref "IC3") (pin "5") (pinfunction "LO_5") (pintype "output"))
      (node (ref "R6") (pin "1") (pinfunction "1_1") (pintype "passive"))
    )
    (net (code "65") (name "Net-(IC3-VB)") (class "Default")
      (node (ref "C3") (pin "1") (pinfunction "1_1") (pintype "passive"))
      (node (ref "D3") (pin "C") (pinfunction "C_C") (pintype "passive"))
      (node (ref "IC3") (pin "8") (pinfunction "VB_8") (pintype "input"))
    )
    (net (code "66") (name "Net-(IC4-HO)") (class "Default")
      (node (ref "IC4") (pin "7") (pinfunction "HO_7") (pintype "output"))
      (node (ref "R7") (pin "1") (pinfunction "1_1") (pintype "passive"))
    )
    (net (code "67") (name "Net-(IC4-LO)") (class "Default")
      (node (ref "IC4") (pin "5") (pinfunction "LO_5") (pintype "output"))
      (node (ref "R8") (pin "1") (pinfunction "1_1") (pintype "passive"))
    )
    (net (code "68") (name "Net-(IC4-VB)") (class "Default")
      (node (ref "C4") (pin "1") (pinfunction "1_1") (pintype "passive"))
      (node (ref "D4") (pin "C") (pinfunction "C_C") (pintype "passive"))
      (node (ref "IC4") (pin "8") (pinfunction "VB_8") (pintype "input"))
    )
    (net (code "69") (name "Net-(IC5-HO)") (class "Default")
      (node (ref "IC5") (pin "7") (pinfunction "HO_7") (pintype "output"))
      (node (ref "R9") (pin "1") (pinfunction "1_1") (pintype "passive"))
    )
    (net (code "70") (name "Net-(IC5-LO)") (class "Default")
      (node (ref "IC5") (pin "5") (pinfunction "LO_5") (pintype "output"))
      (node (ref "R10") (pin "1") (pinfunction "1_1") (pintype "passive"))
    )
    (net (code "71") (name "Net-(IC5-VB)") (class "Default")
      (node (ref "C5") (pin "1") (pinfunction "1_1") (pintype "passive"))
      (node (ref "D5") (pin "C") (pinfunction "C_C") (pintype "passive"))
      (node (ref "IC5") (pin "8") (pinfunction "VB_8") (pintype "input"))
    )
    (net (code "72") (name "Net-(IC6-HO)") (class "Default")
      (node (ref "IC6") (pin "7") (pinfunction "HO_7") (pintype "output"))
      (node (ref "R11") (pin "1") (pinfunction "1_1") (pintype "passive"))
    )
    (net (code "73") (name "Net-(IC6-LO)") (class "Default")
      (node (ref "IC6") (pin "5") (pinfunction "LO_5") (pintype "output"))
      (node (ref "R12") (pin "1") (pinfunction "1_1") (pintype "passive"))
    )
    (net (code "74") (name "Net-(IC6-VB)") (class "Default")
      (node (ref "C6") (pin "1") (pinfunction "1_1") (pintype "passive"))
      (node (ref "D6") (pin "C") (pinfunction "C_C") (pintype "passive"))
      (node (ref "IC6") (pin "8") (pinfunction "VB_8") (pintype "input"))
    )
    (net (code "75") (name "Net-(IC8-NR)") (class "Default")
      (node (ref "C19") (pin "1") (pinfunction "1_1") (pintype "passive"))
      (node (ref "IC8") (pin "4") (pinfunction "NR_4") (pintype "passive"))
    )
    (net (code "76") (name "Net-(IC9-NR)") (class "Default")
      (node (ref "C20") (pin "1") (pinfunction "1_1") (pintype "passive"))
      (node (ref "IC9") (pin "4") (pinfunction "NR_4") (pintype "passive"))
    )
    (net (code "77") (name "Net-(IC10G-PD0{slash}OSC<=)") (class "Default")
      (node (ref "C38") (pin "1") (pinfunction "1_1") (pintype "passive"))
      (node (ref "IC10") (pin "5") (pinfunction "PD0/OSC<=_5") (pintype "bidirectional"))
      (node (ref "X1") (pin "2") (pinfunction "2_2") (pintype "passive"))
    )
    (net (code "78") (name "Net-(IC10G-PD1{slash}OSC=>)") (class "Default")
      (node (ref "C21") (pin "1") (pinfunction "1_1") (pintype "passive"))
      (node (ref "IC10") (pin "6") (pinfunction "PD1/OSC=>_6") (pintype "bidirectional"))
      (node (ref "X1") (pin "1") (pinfunction "1_1") (pintype "passive"))
    )
    (net (code "79") (name "Net-(IC12-CAP+)") (class "Default")
      (node (ref "C29") (pin "1") (pinfunction "1_1") (pintype "passive"))
      (node (ref "IC12") (pin "5") (pinfunction "CAP+_5") (pintype "passive"))
    )
    (net (code "80") (name "Net-(IC12-CAP-)") (class "Default")
      (node (ref "C29") (pin "2") (pinfunction "2_2") (pintype "passive"))
      (node (ref "IC12") (pin "3") (pinfunction "CAP-_3") (pintype "passive"))
    )
    (net (code "81") (name "Net-(IN1-Pad1)") (class "Default")
      (node (ref "IN1") (pin "1") (pinfunction "1_1") (pintype "passive"))
      (node (ref "R25") (pin "2") (pinfunction "2_2") (pintype "passive"))
    )
    (net (code "82") (name "Net-(IN2-Pad1)") (class "Default")
      (node (ref "IN2") (pin "1") (pinfunction "1_1") (pintype "passive"))
      (node (ref "R26") (pin "2") (pinfunction "2_2") (pintype "passive"))
    )
    (net (code "83") (name "Net-(IN3-Pad1)") (class "Default")
      (node (ref "IN3") (pin "1") (pinfunction "1_1") (pintype "passive"))
      (node (ref "R27") (pin "2") (pinfunction "2_2") (pintype "passive"))
    )
    (net (code "84") (name "Net-(IN4-Pad1)") (class "Default")
      (node (ref "IN4") (pin "1") (pinfunction "1_1") (pintype "passive"))
      (node (ref "R28") (pin "2") (pinfunction "2_2") (pintype "passive"))
    )
    (net (code "85") (name "Net-(L1-Pad2)") (class "Default")
      (node (ref "L1") (pin "2") (pinfunction "2_2") (pintype "passive"))
      (node (ref "USB") (pin "1") (pinfunction "1_1") (pintype "passive"))
    )
    (net (code "86") (name "Net-(ON-PadC)") (class "Default")
      (node (ref "ON") (pin "C") (pinfunction "C_C") (pintype "passive"))
      (node (ref "R34") (pin "1") (pinfunction "1_1") (pintype "passive"))
    )
    (net (code "87") (name "Net-(PWR-PadC)") (class "Default")
      (node (ref "PWR") (pin "C") (pinfunction "C_C") (pintype "passive"))
      (node (ref "R18") (pin "1") (pinfunction "1_1") (pintype "passive"))
    )
    (net (code "88") (name "Net-(Q1A-N-G)") (class "Default")
      (node (ref "Q1") (pin "4") (pinfunction "N-G_4") (pintype "passive"))
      (node (ref "R1") (pin "2") (pinfunction "2_2") (pintype "passive"))
    )
    (net (code "89") (name "Net-(Q1B-N-G)") (class "Default")
      (node (ref "Q1") (pin "2") (pinfunction "N-G_2") (pintype "passive"))
      (node (ref "R2") (pin "2") (pinfunction "2_2") (pintype "passive"))
    )
    (net (code "90") (name "Net-(Q2A-N-G)") (class "Default")
      (node (ref "Q2") (pin "4") (pinfunction "N-G_4") (pintype "passive"))
      (node (ref "R3") (pin "2") (pinfunction "2_2") (pintype "passive"))
    )
    (net (code "91") (name "Net-(Q2B-N-G)") (class "Default")
      (node (ref "Q2") (pin "2") (pinfunction "N-G_2") (pintype "passive"))
      (node (ref "R4") (pin "2") (pinfunction "2_2") (pintype "passive"))
    )
    (net (code "92") (name "Net-(Q3A-N-G)") (class "Default")
      (node (ref "Q3") (pin "4") (pinfunction "N-G_4") (pintype "passive"))
      (node (ref "R5") (pin "2") (pinfunction "2_2") (pintype "passive"))
    )
    (net (code "93") (name "Net-(Q3B-N-G)") (class "Default")
      (node (ref "Q3") (pin "2") (pinfunction "N-G_2") (pintype "passive"))
      (node (ref "R6") (pin "2") (pinfunction "2_2") (pintype "passive"))
    )
    (net (code "94") (name "Net-(Q4A-N-G)") (class "Default")
      (node (ref "Q4") (pin "4") (pinfunction "N-G_4") (pintype "passive"))
      (node (ref "R7") (pin "2") (pinfunction "2_2") (pintype "passive"))
    )
    (net (code "95") (name "Net-(Q4B-N-G)") (class "Default")
      (node (ref "Q4") (pin "2") (pinfunction "N-G_2") (pintype "passive"))
      (node (ref "R8") (pin "2") (pinfunction "2_2") (pintype "passive"))
    )
    (net (code "96") (name "Net-(Q5A-N-G)") (class "Default")
      (node (ref "Q5") (pin "4") (pinfunction "N-G_4") (pintype "passive"))
      (node (ref "R9") (pin "2") (pinfunction "2_2") (pintype "passive"))
    )
    (net (code "97") (name "Net-(Q5B-N-G)") (class "Default")
      (node (ref "Q5") (pin "2") (pinfunction "N-G_2") (pintype "passive"))
      (node (ref "R10") (pin "2") (pinfunction "2_2") (pintype "passive"))
    )
    (net (code "98") (name "Net-(Q6A-N-G)") (class "Default")
      (node (ref "Q6") (pin "4") (pinfunction "N-G_4") (pintype "passive"))
      (node (ref "R11") (pin "2") (pinfunction "2_2") (pintype "passive"))
    )
    (net (code "99") (name "Net-(Q6B-N-G)") (class "Default")
      (node (ref "Q6") (pin "2") (pinfunction "N-G_2") (pintype "passive"))
      (node (ref "R12") (pin "2") (pinfunction "2_2") (pintype "passive"))
    )
    (net (code "100") (name "Net-(R13-Pad2)") (class "Default")
      (node (ref "R13") (pin "2") (pinfunction "2_2") (pintype "passive"))
      (node (ref "USB") (pin "2") (pinfunction "2_2") (pintype "passive"))
    )
    (net (code "101") (name "Net-(R14-Pad2)") (class "Default")
      (node (ref "R14") (pin "2") (pinfunction "2_2") (pintype "passive"))
      (node (ref "USB") (pin "3") (pinfunction "3_3") (pintype "passive"))
    )
    (net (code "102") (name "Net-(R32-Pad2)") (class "Default")
      (node (ref "R32") (pin "2") (pinfunction "2_2") (pintype "passive"))
      (node (ref "R33") (pin "1") (pinfunction "1_1") (pintype "passive"))
      (node (ref "T1") (pin "B") (pinfunction "B_B") (pintype "passive"))
    )
    (net (code "103") (name "VCC") (class "Default")
      (node (ref "C11") (pin "+") (pinfunction "+_+") (pintype "passive"))
      (node (ref "C12") (pin "1") (pinfunction "1_1") (pintype "passive"))
      (node (ref "C13") (pin "1") (pinfunction "1_1") (pintype "passive"))
      (node (ref "C14") (pin "+") (pinfunction "+_+") (pintype "passive"))
      (node (ref "C15") (pin "+") (pinfunction "+_+") (pintype "passive"))
      (node (ref "C16") (pin "1") (pinfunction "1_1") (pintype "passive"))
      (node (ref "IC7") (pin "1") (pinfunction "VI_1") (pintype "input"))
      (node (ref "Q1") (pin "5") (pinfunction "N-D_5") (pintype "passive"))
      (node (ref "Q1") (pin "6") (pinfunction "N-D_6") (pintype "passive"))
      (node (ref "Q2") (pin "5") (pinfunction "N-D_5") (pintype "passive"))
      (node (ref "Q2") (pin "6") (pinfunction "N-D_6") (pintype "passive"))
      (node (ref "Q3") (pin "5") (pinfunction "N-D_5") (pintype "passive"))
      (node (ref "Q3") (pin "6") (pinfunction "N-D_6") (pintype "passive"))
      (node (ref "Q4") (pin "5") (pinfunction "N-D_5") (pintype "passive"))
      (node (ref "Q4") (pin "6") (pinfunction "N-D_6") (pintype "passive"))
      (node (ref "Q5") (pin "5") (pinfunction "N-D_5") (pintype "passive"))
      (node (ref "Q5") (pin "6") (pinfunction "N-D_6") (pintype "passive"))
      (node (ref "Q6") (pin "5") (pinfunction "N-D_5") (pintype "passive"))
      (node (ref "Q6") (pin "6") (pinfunction "N-D_6") (pintype "passive"))
      (node (ref "Q7") (pin "1") (pinfunction "P-S_1") (pintype "passive"))
      (node (ref "Q7") (pin "2") (pinfunction "P-S_2") (pintype "passive"))
      (node (ref "Q7") (pin "3") (pinfunction "P-S_3") (pintype "passive"))
      (node (ref "R16") (pin "1") (pinfunction "1_1") (pintype "passive"))
    )
    (net (code "104") (name "unconnected-(USB-Pad4)") (class "Default")
      (node (ref "USB") (pin "4") (pinfunction "4_4") (pintype "passive"))
    )
  )
)
